# rasp_sheild_main.net
KiCad netlist of a schematic drawn in Altium Designer
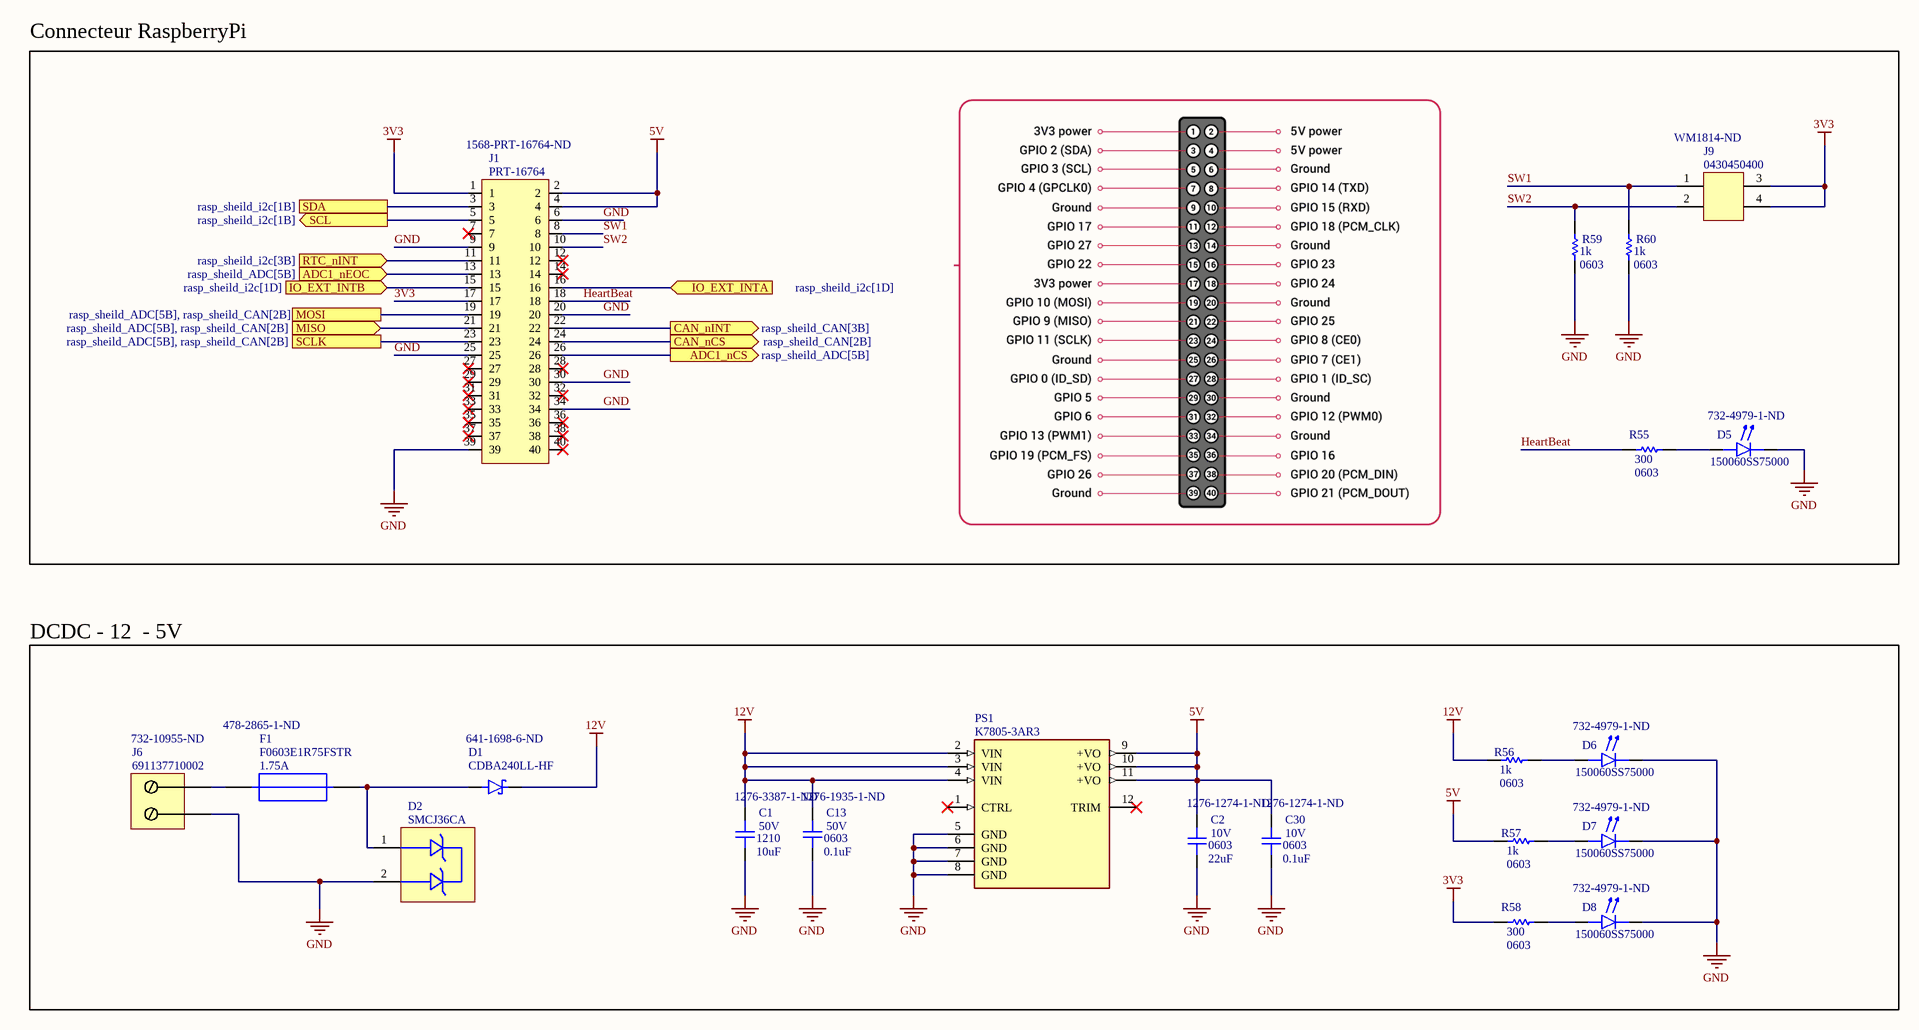
[diagram p0: rasp_sheild_main.SchDoc]

(export (version "E")
  (design (tool "Eeschema 10.0.6"))
  (components
    (comp (ref "C1")
      (value "10uF")
      (footprint "CAP_1210")
      (description "XXX - Description - Package")
      (fields
        (field (name "VOLTAGE RATING") "50V")
        (field (name "PACKAGE") "1210")
        (field (name "SUPPLIER PART NUMBER 1") "1276-3387-1-ND")
        (field (name "Comment") "CL32B106KBJNNNE")
      )
      (libsource (lib "royj1311") (part "CAP_1210"))
    )
    (comp (ref "C2")
      (value "22uF")
      (footprint "CAP_0603")
      (description "XXX - Description - Package")
      (fields
        (field (name "VOLTAGE RATING") "10V")
        (field (name "PACKAGE") "0603")
        (field (name "SUPPLIER PART NUMBER 1") "1276-1274-1-ND")
        (field (name "Comment") "CL10A226MP8NUNE")
      )
      (libsource (lib "royj1311") (part "CAP_0603"))
    )
    (comp (ref "C13")
      (value "0.1uF")
      (footprint "CAP_0603")
      (description "XXX - Description - Package")
      (fields
        (field (name "VOLTAGE RATING") "50V")
        (field (name "PACKAGE") "0603")
        (field (name "SUPPLIER PART NUMBER 1") "1276-1935-1-ND")
        (field (name "Comment") "CL10B104KB8NNWC")
      )
      (libsource (lib "royj1311") (part "CAP_0603"))
    )
    (comp (ref "C30")
      (value "0.1uF")
      (footprint "CAP_0603")
      (description "XXX - Description - Package")
      (fields
        (field (name "VOLTAGE RATING") "10V")
        (field (name "PACKAGE") "0603")
        (field (name "SUPPLIER PART NUMBER 1") "1276-1274-1-ND")
        (field (name "Comment") "CL10A226MP8NUNE")
      )
      (libsource (lib "royj1311") (part "CAP_0603"))
    )
    (comp (ref "D1")
      (value "CDBA240LL-HF")
      (footprint "DO-214")
      (description "Diode 40 V 2A Surface Mount DO-214AC (SMA)")
      (fields (field (name "SUPPLIER PART NUMBER 1") "641-1698-6-ND"))
      (libsource (lib "royj1311") (part "CDBA240LL-HF"))
    )
    (comp (ref "D2")
      (value "SMCJ36CA")
      (footprint "SMCJ36CA")
      (description "44.2V Clamp 25.8A Ipp Tvs Diode Surface Mount DO-214AB (SMC)")
      (libsource (lib "royj1311") (part "SMCJ36CA"))
    )
    (comp (ref "D5")
      (value "150060SS75000")
      (footprint "LED 0603")
      (description "Red 630nm LED Indication - Discrete 1.9V 0603 (1608 Metric)")
      (fields (field (name "SUPPLIER PART NUMBER 1") "732-4979-1-ND"))
      (libsource (lib "royj1311") (part "150060SS75000"))
    )
    (comp (ref "D6")
      (value "150060SS75000")
      (footprint "LED 0603")
      (description "Red 630nm LED Indication - Discrete 1.9V 0603 (1608 Metric)")
      (fields (field (name "SUPPLIER PART NUMBER 1") "732-4979-1-ND"))
      (libsource (lib "royj1311") (part "150060SS75000"))
    )
    (comp (ref "D7")
      (value "150060SS75000")
      (footprint "LED 0603")
      (description "Red 630nm LED Indication - Discrete 1.9V 0603 (1608 Metric)")
      (fields (field (name "SUPPLIER PART NUMBER 1") "732-4979-1-ND"))
      (libsource (lib "royj1311") (part "150060SS75000"))
    )
    (comp (ref "D8")
      (value "150060SS75000")
      (footprint "LED 0603")
      (description "Red 630nm LED Indication - Discrete 1.9V 0603 (1608 Metric)")
      (fields (field (name "SUPPLIER PART NUMBER 1") "732-4979-1-ND"))
      (libsource (lib "royj1311") (part "150060SS75000"))
    )
    (comp (ref "F1")
      (value "F0603E1R75FSTR")
      (footprint "RES_0603")
      (description "1.75 A AC 32 V DC Fuse Board Mount (Cartridge Style Excluded) Surface Mount 0603 (1608 Metric)")
      (fields (field (name "ALTIUM_VALUE") "1.75A") (field (name "SUPPLIER PART NUMBER 1") "478-2865-1-ND"))
      (libsource (lib "royj1311") (part "F0603E1R75FSTR"))
    )
    (comp (ref "J1")
      (value "PRT-16764")
      (footprint "PRT-16764")
      (description "EXTENDED GPIO FEMALE HEADER - 2X")
      (fields (field (name "SUPPLIER PART NUMBER 1") "1568-PRT-16764-ND"))
      (libsource (lib "royj1311") (part "PRT-14275_1"))
    )
    (comp (ref "J6")
      (value "691137710002")
      (footprint "691137710002")
      (description "2 Position Wire to Board Terminal Block Horizontal with Board 0.197\" (5.00mm) Through Hole")
      (fields (field (name "SUPPLIER PART NUMBER 1") "732-10955-ND"))
      (libsource (lib "royj1311") (part "691137710002"))
    )
    (comp (ref "J9")
      (value "0430450400")
      (footprint "0430450400")
      (description "Connector Header Through Hole, Right Angle 4 position 0.118\" (3.00mm)")
      (fields (field (name "SUPPLIER PART NUMBER 1") "WM1814-ND"))
      (libsource (lib "royj1311") (part "0430450400"))
    )
    (comp (ref "PS1")
      (value "K7805-3AR3")
      (footprint "CONV_K7805-3AR3")
      (description "Non-Isolated PoL Module DC DC Converter 1 Output 5V - - - 3A 8V - 36V Input")
      (fields (field (name "MF") "Mornsun America, LLC"))
      (libsource (lib "royj1311") (part "K7805-3AR3"))
    )
    (comp (ref "R55")
      (value "300")
      (footprint "RES_0603")
      (description "XXX - Description - Package")
      (fields (field (name "PACKAGE") "0603") (field (name "Comment") "RC0603JR-07300RL"))
      (libsource (lib "royj1311") (part "RES_0603"))
    )
    (comp (ref "R56")
      (value "1k")
      (footprint "RES_0603")
      (description "XXX - Description - Package")
      (fields (field (name "PACKAGE") "0603") (field (name "Comment") "Part Number"))
      (libsource (lib "royj1311") (part "RES_0603"))
    )
    (comp (ref "R57")
      (value "1k")
      (footprint "RES_0603")
      (description "XXX - Description - Package")
      (fields (field (name "PACKAGE") "0603") (field (name "Comment") "Part Number"))
      (libsource (lib "royj1311") (part "RES_0603"))
    )
    (comp (ref "R58")
      (value "300")
      (footprint "RES_0603")
      (description "XXX - Description - Package")
      (fields (field (name "PACKAGE") "0603") (field (name "Comment") "RC0603JR-07300RL"))
      (libsource (lib "royj1311") (part "RES_0603"))
    )
    (comp (ref "R59")
      (value "1k")
      (footprint "RES_0603")
      (description "XXX - Description - Package")
      (fields (field (name "PACKAGE") "0603") (field (name "Comment") "Part Number"))
      (libsource (lib "royj1311") (part "RES_0603"))
    )
    (comp (ref "R60")
      (value "1k")
      (footprint "RES_0603")
      (description "XXX - Description - Package")
      (fields (field (name "PACKAGE") "0603") (field (name "Comment") "Part Number"))
      (libsource (lib "royj1311") (part "RES_0603"))
    )
  )
  (nets
    (net (code "1") (name "/ADC1_nCS") (class "Default")
      (node (ref "J1") (pin "26") (pinfunction "26_26") (pintype "passive"))
    )
    (net (code "2") (name "/ADC1_nEOC") (class "Default")
      (node (ref "J1") (pin "13") (pinfunction "13_13") (pintype "passive"))
    )
    (net (code "3") (name "/CAN_nCS") (class "Default")
      (node (ref "J1") (pin "24") (pinfunction "24_24") (pintype "passive"))
    )
    (net (code "4") (name "/CAN_nINT") (class "Default")
      (node (ref "J1") (pin "22") (pinfunction "22_22") (pintype "passive"))
    )
    (net (code "5") (name "/HeartBeat") (class "Default")
      (node (ref "J1") (pin "18") (pinfunction "18_18") (pintype "passive"))
      (node (ref "R55") (pin "2") (pinfunction "2_2") (pintype "passive"))
    )
    (net (code "6") (name "/IO_EXT_INTA") (class "Default")
      (node (ref "J1") (pin "16") (pinfunction "16_16") (pintype "passive"))
    )
    (net (code "7") (name "/IO_EXT_INTB") (class "Default")
      (node (ref "J1") (pin "15") (pinfunction "15_15") (pintype "passive"))
    )
    (net (code "8") (name "/MISO") (class "Default")
      (node (ref "J1") (pin "21") (pinfunction "21_21") (pintype "passive"))
    )
    (net (code "9") (name "/MOSI") (class "Default")
      (node (ref "J1") (pin "19") (pinfunction "19_19") (pintype "passive"))
    )
    (net (code "10") (name "/RTC_nINT") (class "Default")
      (node (ref "J1") (pin "11") (pinfunction "11_11") (pintype "passive"))
    )
    (net (code "11") (name "/SCL") (class "Default")
      (node (ref "J1") (pin "5") (pinfunction "5_5") (pintype "passive"))
    )
    (net (code "12") (name "/SCLK") (class "Default")
      (node (ref "J1") (pin "23") (pinfunction "23_23") (pintype "passive"))
    )
    (net (code "13") (name "/SDA") (class "Default")
      (node (ref "J1") (pin "3") (pinfunction "3_3") (pintype "passive"))
    )
    (net (code "14") (name "/SW1") (class "Default")
      (node (ref "J1") (pin "8") (pinfunction "8_8") (pintype "passive"))
      (node (ref "J9") (pin "1") (pinfunction "1_1") (pintype "passive"))
      (node (ref "R60") (pin "2") (pinfunction "2_2") (pintype "passive"))
    )
    (net (code "15") (name "/SW2") (class "Default")
      (node (ref "J1") (pin "10") (pinfunction "10_10") (pintype "passive"))
      (node (ref "J9") (pin "2") (pinfunction "2_2") (pintype "passive"))
      (node (ref "R59") (pin "2") (pinfunction "2_2") (pintype "passive"))
    )
    (net (code "16") (name "3V3") (class "Default")
      (node (ref "J1") (pin "1") (pinfunction "1_1") (pintype "passive"))
      (node (ref "J1") (pin "17") (pinfunction "17_17") (pintype "passive"))
      (node (ref "J9") (pin "3") (pinfunction "3_3") (pintype "passive"))
      (node (ref "J9") (pin "4") (pinfunction "4_4") (pintype "passive"))
      (node (ref "R58") (pin "2") (pinfunction "2_2") (pintype "passive"))
    )
    (net (code "17") (name "5V") (class "Default")
      (node (ref "C2") (pin "2") (pinfunction "2_2") (pintype "passive"))
      (node (ref "C30") (pin "2") (pinfunction "2_2") (pintype "passive"))
      (node (ref "J1") (pin "2") (pinfunction "2_2") (pintype "passive"))
      (node (ref "J1") (pin "4") (pinfunction "4_4") (pintype "passive"))
      (node (ref "PS1") (pin "10") (pinfunction "+VO_10") (pintype "output"))
      (node (ref "PS1") (pin "11") (pinfunction "+VO_11") (pintype "output"))
      (node (ref "PS1") (pin "9") (pinfunction "+VO_9") (pintype "output"))
      (node (ref "R57") (pin "2") (pinfunction "2_2") (pintype "passive"))
    )
    (net (code "18") (name "12V") (class "Default")
      (node (ref "C1") (pin "2") (pinfunction "2_2") (pintype "passive"))
      (node (ref "C13") (pin "2") (pinfunction "2_2") (pintype "passive"))
      (node (ref "D1") (pin "C") (pinfunction "K_C") (pintype "passive"))
      (node (ref "PS1") (pin "2") (pinfunction "VIN_2") (pintype "input"))
      (node (ref "PS1") (pin "3") (pinfunction "VIN_3") (pintype "input"))
      (node (ref "PS1") (pin "4") (pinfunction "VIN_4") (pintype "input"))
      (node (ref "R56") (pin "2") (pinfunction "2_2") (pintype "passive"))
    )
    (net (code "19") (name "GND") (class "Default")
      (node (ref "C1") (pin "1") (pinfunction "1_1") (pintype "passive"))
      (node (ref "C13") (pin "1") (pinfunction "1_1") (pintype "passive"))
      (node (ref "C2") (pin "1") (pinfunction "1_1") (pintype "passive"))
      (node (ref "C30") (pin "1") (pinfunction "1_1") (pintype "passive"))
      (node (ref "D2") (pin "2") (pinfunction "2_2") (pintype "passive"))
      (node (ref "D5") (pin "K") (pinfunction "K_K") (pintype "passive"))
      (node (ref "D6") (pin "K") (pinfunction "K_K") (pintype "passive"))
      (node (ref "D7") (pin "K") (pinfunction "K_K") (pintype "passive"))
      (node (ref "D8") (pin "K") (pinfunction "K_K") (pintype "passive"))
      (node (ref "J1") (pin "20") (pinfunction "20_20") (pintype "passive"))
      (node (ref "J1") (pin "25") (pinfunction "25_25") (pintype "passive"))
      (node (ref "J1") (pin "30") (pinfunction "30_30") (pintype "passive"))
      (node (ref "J1") (pin "34") (pinfunction "34_34") (pintype "passive"))
      (node (ref "J1") (pin "39") (pinfunction "39_39") (pintype "passive"))
      (node (ref "J1") (pin "6") (pinfunction "6_6") (pintype "passive"))
      (node (ref "J1") (pin "9") (pinfunction "9_9") (pintype "passive"))
      (node (ref "J6") (pin "2") (pinfunction "2_2") (pintype "passive"))
      (node (ref "PS1") (pin "5") (pinfunction "GND_5") (pintype "power_in"))
      (node (ref "PS1") (pin "6") (pinfunction "GND_6") (pintype "power_in"))
      (node (ref "PS1") (pin "7") (pinfunction "GND_7") (pintype "power_in"))
      (node (ref "PS1") (pin "8") (pinfunction "GND_8") (pintype "power_in"))
      (node (ref "R59") (pin "1") (pinfunction "1_1") (pintype "passive"))
      (node (ref "R60") (pin "1") (pinfunction "1_1") (pintype "passive"))
    )
    (net (code "20") (name "Net-(D1-PadA)") (class "Default")
      (node (ref "D1") (pin "A") (pinfunction "A_A") (pintype "passive"))
      (node (ref "D2") (pin "1") (pinfunction "1_1") (pintype "passive"))
      (node (ref "F1") (pin "2") (pinfunction "2_2") (pintype "passive"))
    )
    (net (code "21") (name "Net-(D5-PadA)") (class "Default")
      (node (ref "D5") (pin "A") (pinfunction "A_A") (pintype "passive"))
      (node (ref "R55") (pin "1") (pinfunction "1_1") (pintype "passive"))
    )
    (net (code "22") (name "Net-(D6-PadA)") (class "Default")
      (node (ref "D6") (pin "A") (pinfunction "A_A") (pintype "passive"))
      (node (ref "R56") (pin "1") (pinfunction "1_1") (pintype "passive"))
    )
    (net (code "23") (name "Net-(D7-PadA)") (class "Default")
      (node (ref "D7") (pin "A") (pinfunction "A_A") (pintype "passive"))
      (node (ref "R57") (pin "1") (pinfunction "1_1") (pintype "passive"))
    )
    (net (code "24") (name "Net-(D8-PadA)") (class "Default")
      (node (ref "D8") (pin "A") (pinfunction "A_A") (pintype "passive"))
      (node (ref "R58") (pin "1") (pinfunction "1_1") (pintype "passive"))
    )
    (net (code "25") (name "Net-(F1-Pad1)") (class "Default")
      (node (ref "F1") (pin "1") (pinfunction "1_1") (pintype "passive"))
      (node (ref "J6") (pin "1") (pinfunction "1_1") (pintype "passive"))
    )
    (net (code "26") (name "unconnected-(J1-Pad7)") (class "Default")
      (node (ref "J1") (pin "7") (pinfunction "7_7") (pintype "passive+no_connect"))
    )
    (net (code "27") (name "unconnected-(J1-Pad12)") (class "Default")
      (node (ref "J1") (pin "12") (pinfunction "12_12") (pintype "passive+no_connect"))
    )
    (net (code "28") (name "unconnected-(J1-Pad14)") (class "Default")
      (node (ref "J1") (pin "14") (pinfunction "14_14") (pintype "passive+no_connect"))
    )
    (net (code "29") (name "unconnected-(J1-Pad27)") (class "Default")
      (node (ref "J1") (pin "27") (pinfunction "27_27") (pintype "passive+no_connect"))
    )
    (net (code "30") (name "unconnected-(J1-Pad28)") (class "Default")
      (node (ref "J1") (pin "28") (pinfunction "28_28") (pintype "passive+no_connect"))
    )
    (net (code "31") (name "unconnected-(J1-Pad29)") (class "Default")
      (node (ref "J1") (pin "29") (pinfunction "29_29") (pintype "passive+no_connect"))
    )
    (net (code "32") (name "unconnected-(J1-Pad31)") (class "Default")
      (node (ref "J1") (pin "31") (pinfunction "31_31") (pintype "passive+no_connect"))
    )
    (net (code "33") (name "unconnected-(J1-Pad32)") (class "Default")
      (node (ref "J1") (pin "32") (pinfunction "32_32") (pintype "passive+no_connect"))
    )
    (net (code "34") (name "unconnected-(J1-Pad33)") (class "Default")
      (node (ref "J1") (pin "33") (pinfunction "33_33") (pintype "passive+no_connect"))
    )
    (net (code "35") (name "unconnected-(J1-Pad35)") (class "Default")
      (node (ref "J1") (pin "35") (pinfunction "35_35") (pintype "passive+no_connect"))
    )
    (net (code "36") (name "unconnected-(J1-Pad36)") (class "Default")
      (node (ref "J1") (pin "36") (pinfunction "36_36") (pintype "passive+no_connect"))
    )
    (net (code "37") (name "unconnected-(J1-Pad37)") (class "Default")
      (node (ref "J1") (pin "37") (pinfunction "37_37") (pintype "passive+no_connect"))
    )
    (net (code "38") (name "unconnected-(J1-Pad38)") (class "Default")
      (node (ref "J1") (pin "38") (pinfunction "38_38") (pintype "passive+no_connect"))
    )
    (net (code "39") (name "unconnected-(J1-Pad40)") (class "Default")
      (node (ref "J1") (pin "40") (pinfunction "40_40") (pintype "passive+no_connect"))
    )
    (net (code "40") (name "unconnected-(PS1-CTRL-Pad1)") (class "Default")
      (node (ref "PS1") (pin "1") (pinfunction "CTRL_1") (pintype "input+no_connect"))
    )
    (net (code "41") (name "unconnected-(PS1-TRIM-Pad12)") (class "Default")
      (node (ref "PS1") (pin "12") (pinfunction "TRIM_12") (pintype "passive+no_connect"))
    )
  )
)
